# MicroController.net
KiCad netlist of a schematic drawn in Altium Designer
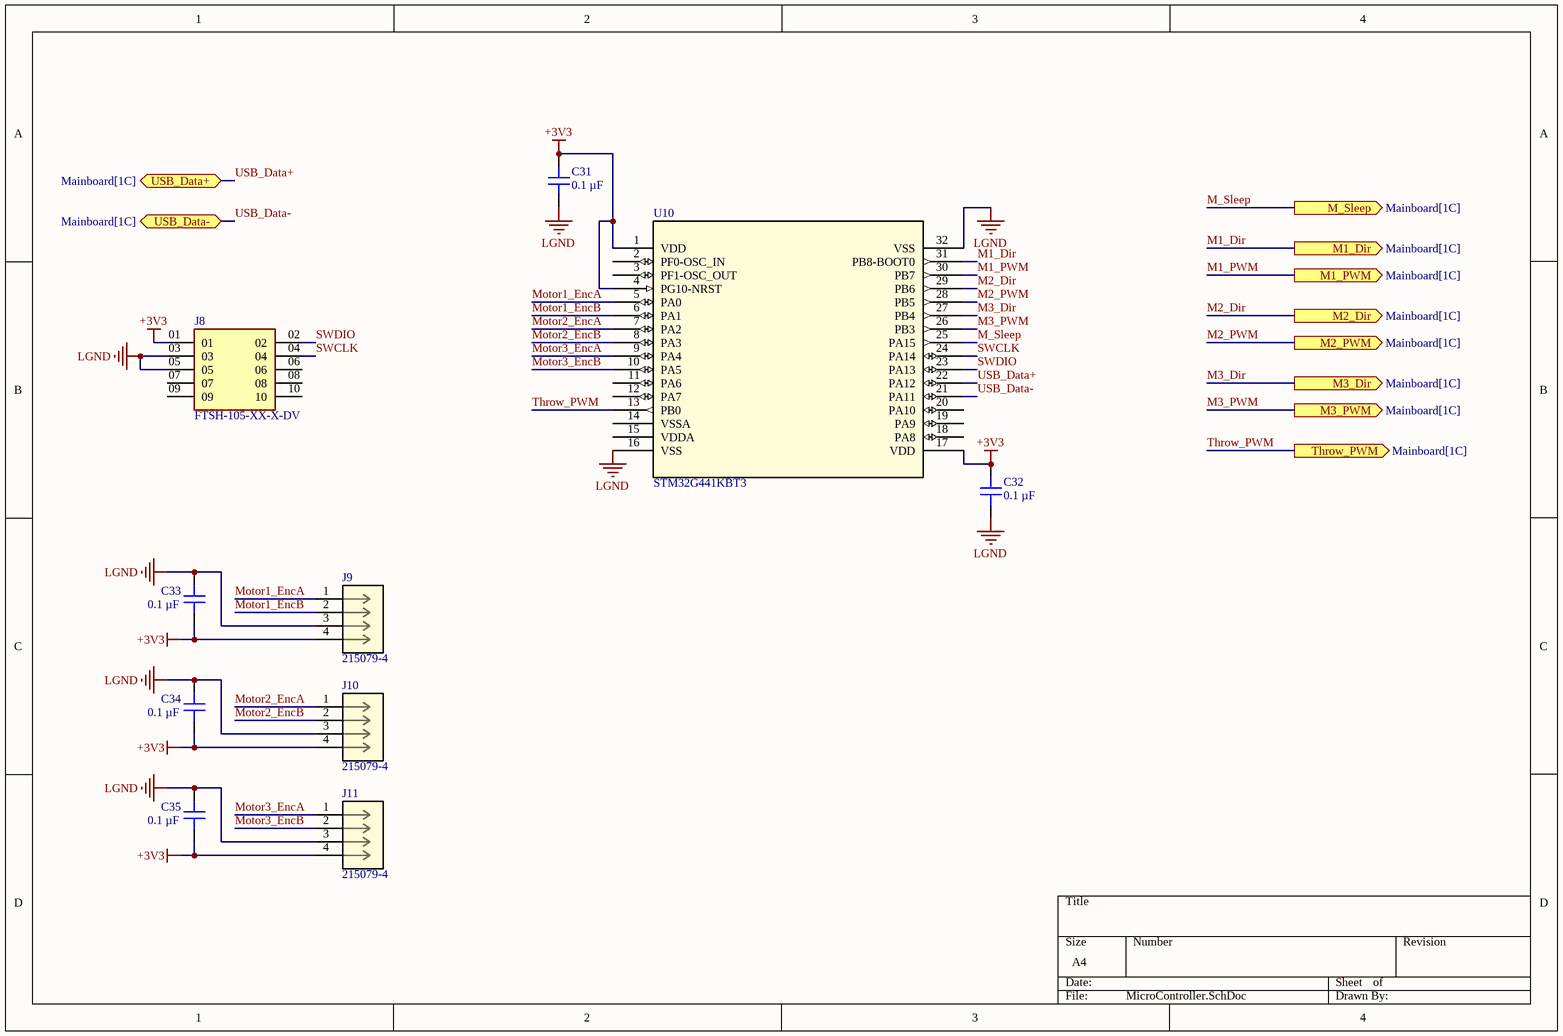
[diagram p0: MicroController.SchDoc]

(export (version "E")
  (design (tool "Eeschema 10.0.6"))
  (components
    (comp (ref "C31")
      (value "0.1 µF")
      (footprint "CAP 1206_3216 - 0.8MM")
      (description "CAP CER 0.1UF 50V Y5V 1206")
      (fields (field (name "PART NUMBER") "CC1206MRY5V9BB104") (field (name "MANUFACTURER") "Yageo"))
      (libsource (lib "Celestial Altium Library - altium_library") (part "Capacitor"))
    )
    (comp (ref "C32")
      (value "0.1 µF")
      (footprint "CAP 1206_3216 - 0.8MM")
      (description "CAP CER 0.1UF 50V Y5V 1206")
      (fields (field (name "PART NUMBER") "CC1206MRY5V9BB104") (field (name "MANUFACTURER") "Yageo"))
      (libsource (lib "Celestial Altium Library - altium_library") (part "Capacitor"))
    )
    (comp (ref "C33")
      (value "0.1 µF")
      (footprint "CAP 1206_3216 - 0.8MM")
      (description "CAP CER 0.1UF 50V Y5V 1206")
      (fields (field (name "PART NUMBER") "CC1206MRY5V9BB104") (field (name "MANUFACTURER") "Yageo"))
      (libsource (lib "Celestial Altium Library - altium_library") (part "Capacitor"))
    )
    (comp (ref "C34")
      (value "0.1 µF")
      (footprint "CAP 1206_3216 - 0.8MM")
      (description "CAP CER 0.1UF 50V Y5V 1206")
      (fields (field (name "PART NUMBER") "CC1206MRY5V9BB104") (field (name "MANUFACTURER") "Yageo"))
      (libsource (lib "Celestial Altium Library - altium_library") (part "Capacitor"))
    )
    (comp (ref "C35")
      (value "0.1 µF")
      (footprint "CAP 1206_3216 - 0.8MM")
      (description "CAP CER 0.1UF 50V Y5V 1206")
      (fields (field (name "PART NUMBER") "CC1206MRY5V9BB104") (field (name "MANUFACTURER") "Yageo"))
      (libsource (lib "Celestial Altium Library - altium_library") (part "Capacitor"))
    )
    (comp (ref "J8")
      (value "FTSH-105-XX-X-DV")
      (footprint "SAMTEC_FTSH-105-XX-X-DV")
      (description "Connector Header Surface Mount 10 position 0.050\" (1.27mm)")
      (libsource (lib "Tartu University") (part "FTSH-105-XX-X-DV"))
    )
    (comp (ref "J9")
      (value "215079-4")
      (footprint "CONN_215079-4_TYC")
      (description "No Description Available")
      (fields (field (name "COPYRIGHT") "Copyright (C) 2022 Ultra Librarian. All rights reserved."))
      (libsource (lib "Tartu University") (part "215079-4"))
    )
    (comp (ref "J10")
      (value "215079-4")
      (footprint "CONN_215079-4_TYC")
      (description "No Description Available")
      (fields (field (name "COPYRIGHT") "Copyright (C) 2022 Ultra Librarian. All rights reserved."))
      (libsource (lib "Tartu University") (part "215079-4"))
    )
    (comp (ref "J11")
      (value "215079-4")
      (footprint "CONN_215079-4_TYC")
      (description "No Description Available")
      (fields (field (name "COPYRIGHT") "Copyright (C) 2022 Ultra Librarian. All rights reserved."))
      (libsource (lib "Tartu University") (part "215079-4"))
    )
    (comp (ref "U10")
      (value "STM32G441KBT3")
      (footprint "LQFP32_7X7_STM")
      (description "No Description Available")
      (fields (field (name "COPYRIGHT") "Copyright (C) 2022 Ultra Librarian. All rights reserved."))
      (libsource (lib "STM32G441KBT3") (part "STM32G441KBT3"))
    )
  )
  (nets
    (net (code "1") (name "+3V3") (class "Default")
      (node (ref "C31") (pin "2") (pinfunction "2_2") (pintype "passive"))
      (node (ref "C32") (pin "2") (pinfunction "2_2") (pintype "passive"))
      (node (ref "C33") (pin "1") (pinfunction "1_1") (pintype "passive"))
      (node (ref "C34") (pin "1") (pinfunction "1_1") (pintype "passive"))
      (node (ref "C35") (pin "1") (pinfunction "1_1") (pintype "passive"))
      (node (ref "J10") (pin "4") (pinfunction "4_4") (pintype "passive"))
      (node (ref "J11") (pin "4") (pinfunction "4_4") (pintype "passive"))
      (node (ref "J8") (pin "01") (pinfunction "01_01") (pintype "passive"))
      (node (ref "J9") (pin "4") (pinfunction "4_4") (pintype "passive"))
      (node (ref "U10") (pin "1") (pinfunction "VDD_1") (pintype "power_in"))
      (node (ref "U10") (pin "17") (pinfunction "VDD_17") (pintype "power_in"))
      (node (ref "U10") (pin "4") (pinfunction "PG10-NRST_4") (pintype "input"))
    )
    (net (code "2") (name "/M1_Dir") (class "Default")
      (node (ref "U10") (pin "31") (pinfunction "PB8-BOOT0_31") (pintype "output"))
    )
    (net (code "3") (name "/M1_PWM") (class "Default")
      (node (ref "U10") (pin "30") (pinfunction "PB7_30") (pintype "output"))
    )
    (net (code "4") (name "/M2_Dir") (class "Default")
      (node (ref "U10") (pin "29") (pinfunction "PB6_29") (pintype "output"))
    )
    (net (code "5") (name "/M2_PWM") (class "Default")
      (node (ref "U10") (pin "28") (pinfunction "PB5_28") (pintype "output"))
    )
    (net (code "6") (name "/M3_Dir") (class "Default")
      (node (ref "U10") (pin "27") (pinfunction "PB4_27") (pintype "output"))
    )
    (net (code "7") (name "/M3_PWM") (class "Default")
      (node (ref "U10") (pin "26") (pinfunction "PB3_26") (pintype "output"))
    )
    (net (code "8") (name "/M_Sleep") (class "Default")
      (node (ref "U10") (pin "25") (pinfunction "PA15_25") (pintype "output"))
    )
    (net (code "9") (name "/Motor1_EncA") (class "Default")
      (node (ref "J9") (pin "1") (pinfunction "1_1") (pintype "passive"))
      (node (ref "U10") (pin "5") (pinfunction "PA0_5") (pintype "bidirectional"))
    )
    (net (code "10") (name "/Motor1_EncB") (class "Default")
      (node (ref "J9") (pin "2") (pinfunction "2_2") (pintype "passive"))
      (node (ref "U10") (pin "6") (pinfunction "PA1_6") (pintype "bidirectional"))
    )
    (net (code "11") (name "/Motor2_EncA") (class "Default")
      (node (ref "J10") (pin "1") (pinfunction "1_1") (pintype "passive"))
      (node (ref "U10") (pin "7") (pinfunction "PA2_7") (pintype "bidirectional"))
    )
    (net (code "12") (name "/Motor2_EncB") (class "Default")
      (node (ref "J10") (pin "2") (pinfunction "2_2") (pintype "passive"))
      (node (ref "U10") (pin "8") (pinfunction "PA3_8") (pintype "bidirectional"))
    )
    (net (code "13") (name "/Motor3_EncA") (class "Default")
      (node (ref "J11") (pin "1") (pinfunction "1_1") (pintype "passive"))
      (node (ref "U10") (pin "9") (pinfunction "PA4_9") (pintype "bidirectional"))
    )
    (net (code "14") (name "/Motor3_EncB") (class "Default")
      (node (ref "J11") (pin "2") (pinfunction "2_2") (pintype "passive"))
      (node (ref "U10") (pin "10") (pinfunction "PA5_10") (pintype "bidirectional"))
    )
    (net (code "15") (name "/SWCLK") (class "Default")
      (node (ref "J8") (pin "04") (pinfunction "04_04") (pintype "passive"))
      (node (ref "U10") (pin "24") (pinfunction "PA14_24") (pintype "bidirectional"))
    )
    (net (code "16") (name "/SWDIO") (class "Default")
      (node (ref "J8") (pin "02") (pinfunction "02_02") (pintype "passive"))
      (node (ref "U10") (pin "23") (pinfunction "PA13_23") (pintype "bidirectional"))
    )
    (net (code "17") (name "/Throw_PWM") (class "Default")
      (node (ref "U10") (pin "13") (pinfunction "PB0_13") (pintype "output"))
    )
    (net (code "18") (name "/USB_Data+") (class "Default")
      (node (ref "U10") (pin "22") (pinfunction "PA12_22") (pintype "bidirectional"))
    )
    (net (code "19") (name "/USB_Data-") (class "Default")
      (node (ref "U10") (pin "21") (pinfunction "PA11_21") (pintype "bidirectional"))
    )
    (net (code "20") (name "LGND") (class "Default")
      (node (ref "C31") (pin "1") (pinfunction "1_1") (pintype "passive"))
      (node (ref "C32") (pin "1") (pinfunction "1_1") (pintype "passive"))
      (node (ref "C33") (pin "2") (pinfunction "2_2") (pintype "passive"))
      (node (ref "C34") (pin "2") (pinfunction "2_2") (pintype "passive"))
      (node (ref "C35") (pin "2") (pinfunction "2_2") (pintype "passive"))
      (node (ref "J10") (pin "3") (pinfunction "3_3") (pintype "passive"))
      (node (ref "J11") (pin "3") (pinfunction "3_3") (pintype "passive"))
      (node (ref "J8") (pin "03") (pinfunction "03_03") (pintype "passive"))
      (node (ref "J8") (pin "05") (pinfunction "05_05") (pintype "passive"))
      (node (ref "J9") (pin "3") (pinfunction "3_3") (pintype "passive"))
      (node (ref "U10") (pin "16") (pinfunction "VSS_16") (pintype "passive"))
      (node (ref "U10") (pin "32") (pinfunction "VSS_32") (pintype "passive"))
    )
    (net (code "21") (name "unconnected-(J8-Pad06)") (class "Default")
      (node (ref "J8") (pin "06") (pinfunction "06_06") (pintype "passive"))
    )
    (net (code "22") (name "unconnected-(J8-Pad07)") (class "Default")
      (node (ref "J8") (pin "07") (pinfunction "07_07") (pintype "passive"))
    )
    (net (code "23") (name "unconnected-(J8-Pad08)") (class "Default")
      (node (ref "J8") (pin "08") (pinfunction "08_08") (pintype "passive"))
    )
    (net (code "24") (name "unconnected-(J8-Pad09)") (class "Default")
      (node (ref "J8") (pin "09") (pinfunction "09_09") (pintype "passive"))
    )
    (net (code "25") (name "unconnected-(J8-Pad10)") (class "Default")
      (node (ref "J8") (pin "10") (pinfunction "10_10") (pintype "passive"))
    )
    (net (code "26") (name "unconnected-(U10-PA6-Pad11)") (class "Default")
      (node (ref "U10") (pin "11") (pinfunction "PA6_11") (pintype "bidirectional"))
    )
    (net (code "27") (name "unconnected-(U10-PA7-Pad12)") (class "Default")
      (node (ref "U10") (pin "12") (pinfunction "PA7_12") (pintype "bidirectional"))
    )
    (net (code "28") (name "unconnected-(U10-PA8-Pad18)") (class "Default")
      (node (ref "U10") (pin "18") (pinfunction "PA8_18") (pintype "bidirectional"))
    )
    (net (code "29") (name "unconnected-(U10-PA9-Pad19)") (class "Default")
      (node (ref "U10") (pin "19") (pinfunction "PA9_19") (pintype "bidirectional"))
    )
    (net (code "30") (name "unconnected-(U10-PA10-Pad20)") (class "Default")
      (node (ref "U10") (pin "20") (pinfunction "PA10_20") (pintype "bidirectional"))
    )
    (net (code "31") (name "unconnected-(U10-PF0-OSC_IN-Pad2)") (class "Default")
      (node (ref "U10") (pin "2") (pinfunction "PF0-OSC_IN_2") (pintype "bidirectional"))
    )
    (net (code "32") (name "unconnected-(U10-PF1-OSC_OUT-Pad3)") (class "Default")
      (node (ref "U10") (pin "3") (pinfunction "PF1-OSC_OUT_3") (pintype "bidirectional"))
    )
    (net (code "33") (name "unconnected-(U10-VDDA-Pad15)") (class "Default")
      (node (ref "U10") (pin "15") (pinfunction "VDDA_15") (pintype "power_in"))
    )
    (net (code "34") (name "unconnected-(U10-VSSA-Pad14)") (class "Default")
      (node (ref "U10") (pin "14") (pinfunction "VSSA_14") (pintype "passive"))
    )
  )
)
